# debugino.net
KiCad netlist of a schematic drawn in EAGLE
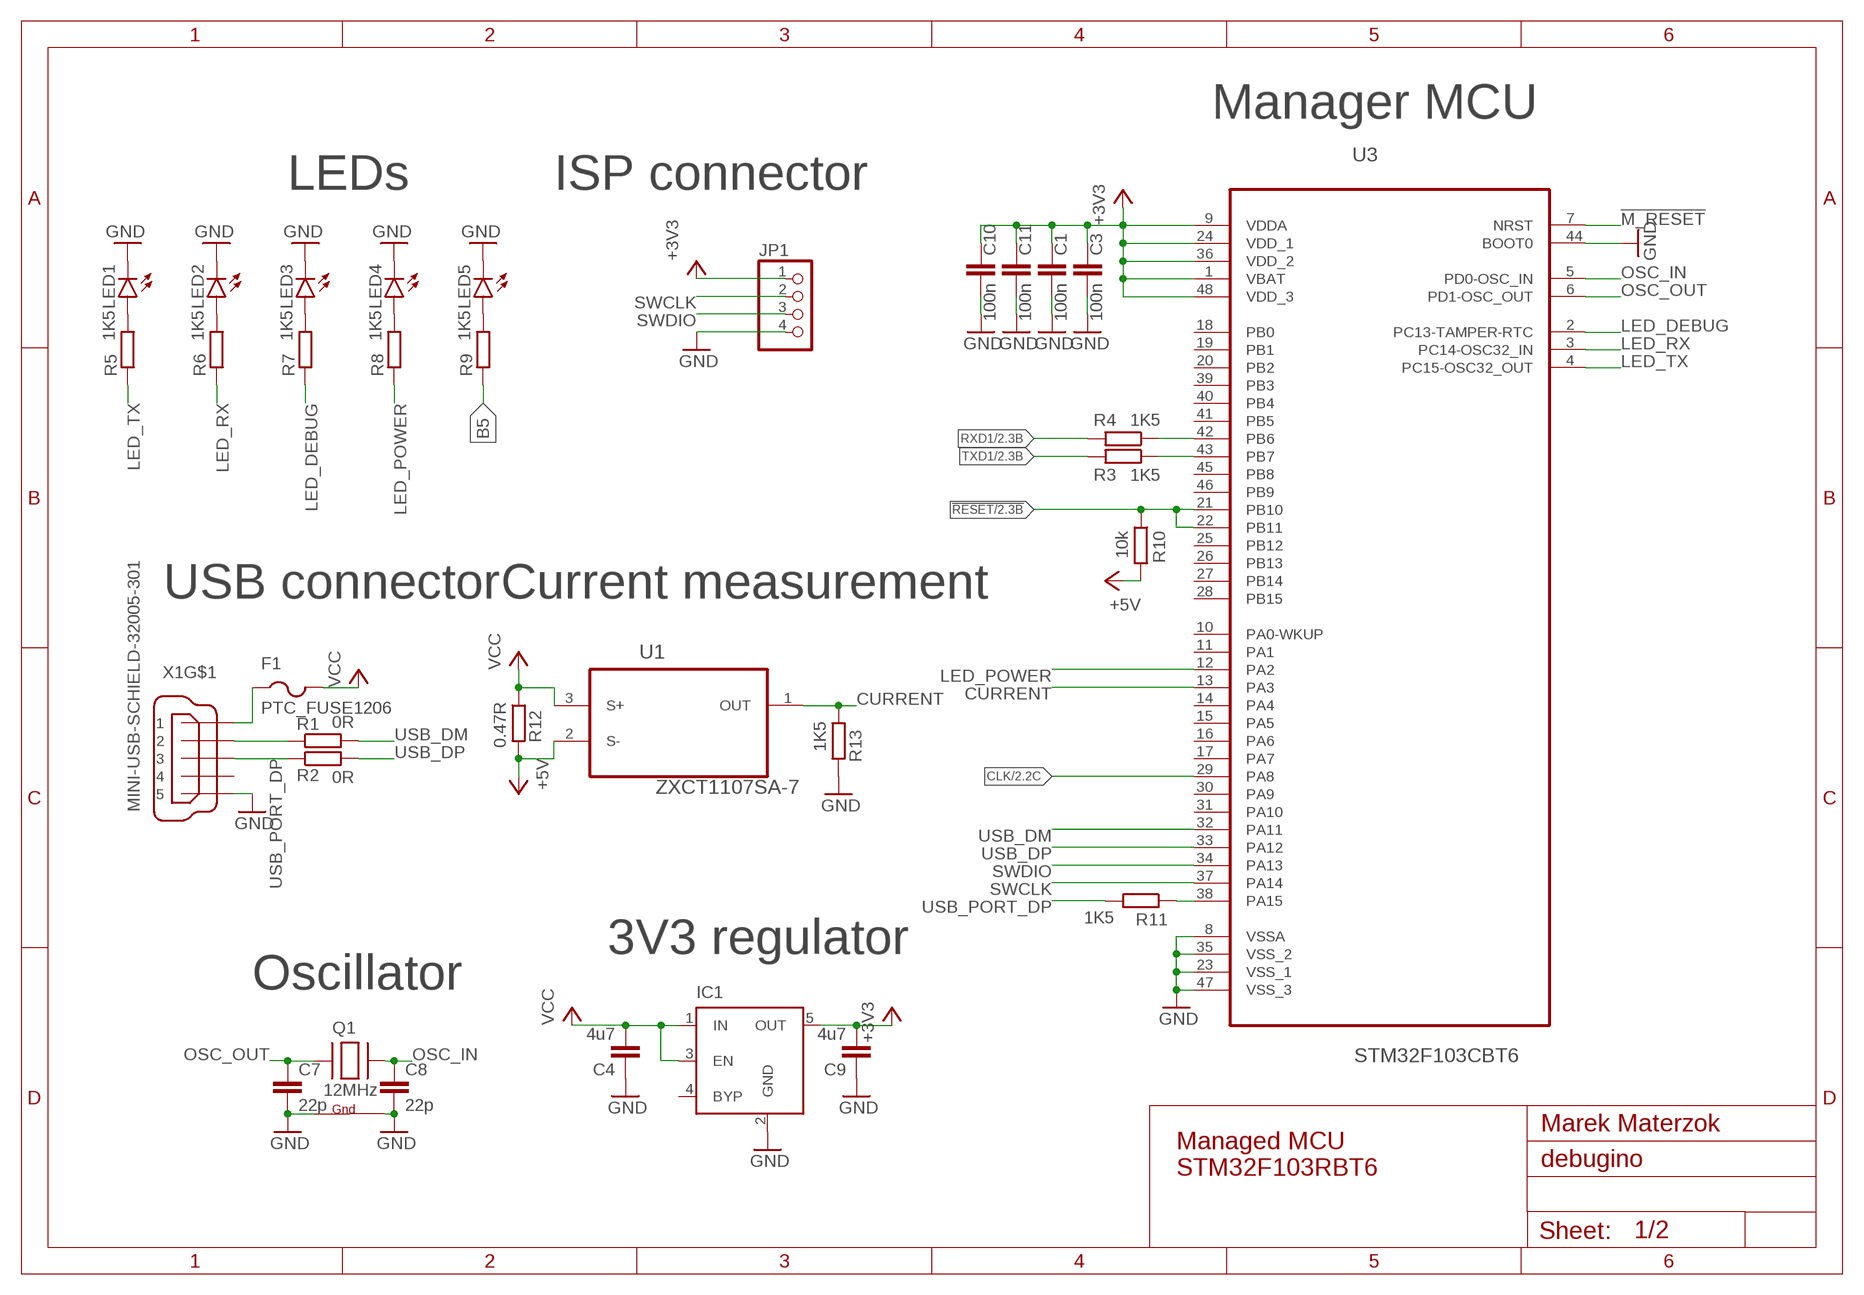
[diagram p0: schematic, sheet 1]
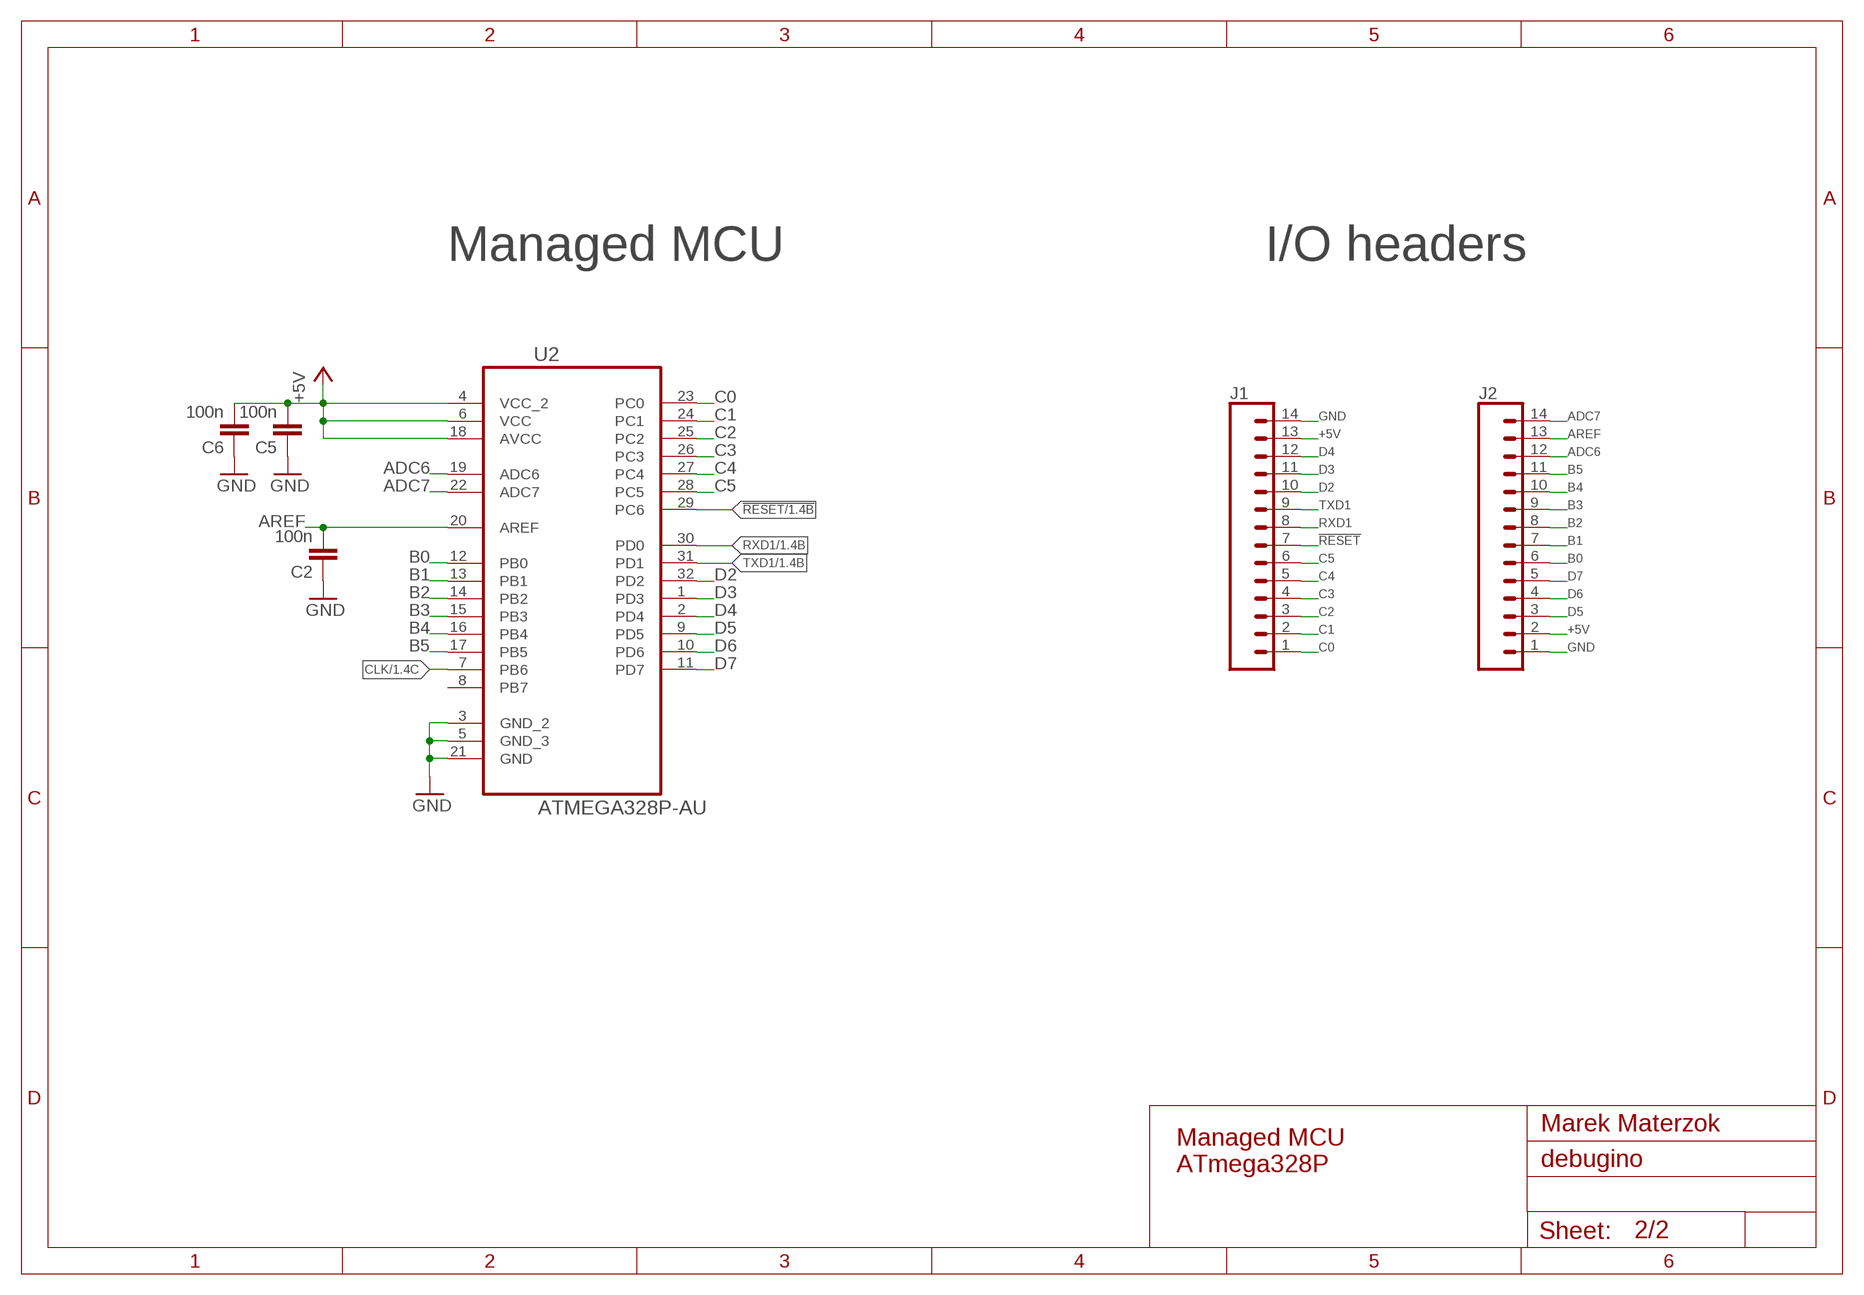
[diagram p1: schematic, sheet 2]

(export (version "E")
  (design (tool "Eeschema 10.0.6"))
  (components
    (comp (ref "C1")
      (value "100n")
      (footprint "eagle-import:CAPC1008X70M")
      (libsource (lib "eagle-import") (part "CAPACITOR0402"))
    )
    (comp (ref "C3")
      (value "100n")
      (footprint "eagle-import:CAPC1008X70M")
      (libsource (lib "eagle-import") (part "CAPACITOR0402"))
    )
    (comp (ref "C4")
      (value "4u7")
      (footprint "eagle-import:CAPC1608X100M")
      (libsource (lib "eagle-import") (part "CAPACITOR0603"))
    )
    (comp (ref "C7")
      (value "22p")
      (footprint "eagle-import:CAPC1008X70M")
      (libsource (lib "eagle-import") (part "CAPACITOR0402"))
    )
    (comp (ref "C8")
      (value "22p")
      (footprint "eagle-import:CAPC1008X70M")
      (libsource (lib "eagle-import") (part "CAPACITOR0402"))
    )
    (comp (ref "C9")
      (value "4u7")
      (footprint "eagle-import:CAPC1608X100M")
      (libsource (lib "eagle-import") (part "CAPACITOR0603"))
    )
    (comp (ref "C10")
      (value "100n")
      (footprint "eagle-import:CAPC1008X70M")
      (libsource (lib "eagle-import") (part "CAPACITOR0402"))
    )
    (comp (ref "C11")
      (value "100n")
      (footprint "eagle-import:CAPC1008X70M")
      (libsource (lib "eagle-import") (part "CAPACITOR0402"))
    )
    (comp (ref "F1")
      (value "PTC_FUSE1206")
      (footprint "eagle-import:FUSC3216X100M")
      (libsource (lib "eagle-import") (part "PTC_FUSE1206"))
    )
    (comp (ref "IC1")
      (value "MIC5219XX")
      (footprint "eagle-import:SOT23-5")
      (libsource (lib "eagle-import") (part "MIC5219XX"))
    )
    (comp (ref "JP1")
      (value "PINHD-1X4")
      (footprint "eagle-import:1X04")
      (libsource (lib "eagle-import") (part "PINHD-1X4"))
    )
    (comp (ref "LED1")
      (value "LEDCHIP-LED0603")
      (footprint "eagle-import:CHIP-LED0603")
      (libsource (lib "eagle-import") (part "LEDCHIP-LED0603"))
    )
    (comp (ref "LED2")
      (value "LEDCHIP-LED0603")
      (footprint "eagle-import:CHIP-LED0603")
      (libsource (lib "eagle-import") (part "LEDCHIP-LED0603"))
    )
    (comp (ref "LED3")
      (value "LEDCHIP-LED0603")
      (footprint "eagle-import:CHIP-LED0603")
      (libsource (lib "eagle-import") (part "LEDCHIP-LED0603"))
    )
    (comp (ref "LED4")
      (value "LEDCHIP-LED0603")
      (footprint "eagle-import:CHIP-LED0603")
      (libsource (lib "eagle-import") (part "LEDCHIP-LED0603"))
    )
    (comp (ref "LED5")
      (value "LEDCHIP-LED0603")
      (footprint "eagle-import:CHIP-LED0603")
      (libsource (lib "eagle-import") (part "LEDCHIP-LED0603"))
    )
    (comp (ref "Q1")
      (value "12MHz")
      (footprint "eagle-import:NX3225")
      (libsource (lib "eagle-import") (part "XTAL-4-3225"))
    )
    (comp (ref "R1")
      (value "0R")
      (footprint "eagle-import:RESC1608X55M")
      (libsource (lib "eagle-import") (part "RESISTOR0603"))
    )
    (comp (ref "R2")
      (value "0R")
      (footprint "eagle-import:RESC1608X55M")
      (libsource (lib "eagle-import") (part "RESISTOR0603"))
    )
    (comp (ref "R3")
      (value "1K5")
      (footprint "eagle-import:RESC1608X55M")
      (libsource (lib "eagle-import") (part "RESISTOR0603"))
    )
    (comp (ref "R4")
      (value "1K5")
      (footprint "eagle-import:RESC1608X55M")
      (libsource (lib "eagle-import") (part "RESISTOR0603"))
    )
    (comp (ref "R5")
      (value "1K5")
      (footprint "eagle-import:RESC1608X55M")
      (libsource (lib "eagle-import") (part "RESISTOR0603"))
    )
    (comp (ref "R6")
      (value "1K5")
      (footprint "eagle-import:RESC1608X55M")
      (libsource (lib "eagle-import") (part "RESISTOR0603"))
    )
    (comp (ref "R7")
      (value "1K5")
      (footprint "eagle-import:RESC1608X55M")
      (libsource (lib "eagle-import") (part "RESISTOR0603"))
    )
    (comp (ref "R8")
      (value "1K5")
      (footprint "eagle-import:RESC1608X55M")
      (libsource (lib "eagle-import") (part "RESISTOR0603"))
    )
    (comp (ref "R9")
      (value "1K5")
      (footprint "eagle-import:RESC1608X55M")
      (libsource (lib "eagle-import") (part "RESISTOR0603"))
    )
    (comp (ref "R10")
      (value "10k")
      (footprint "eagle-import:RESC1608X55M")
      (libsource (lib "eagle-import") (part "RESISTOR0603"))
    )
    (comp (ref "R11")
      (value "1K5")
      (footprint "eagle-import:RESC1608X55M")
      (libsource (lib "eagle-import") (part "RESISTOR0603"))
    )
    (comp (ref "R12")
      (value "0.47R")
      (footprint "eagle-import:RESC2012X65M")
      (libsource (lib "eagle-import") (part "RESISTOR0805"))
    )
    (comp (ref "R13")
      (value "1K5")
      (footprint "eagle-import:RESC1608X55M")
      (libsource (lib "eagle-import") (part "RESISTOR0603"))
    )
    (comp (ref "U1")
      (value "ZXCT1107SA-7")
      (footprint "eagle-import:SOT91P240X110-3N")
      (libsource (lib "eagle-import") (part "ZXCT1107SA-7"))
    )
    (comp (ref "U3")
      (value "STM32F103CBT6")
      (footprint "eagle-import:QFP50P900X900X160-48N")
      (libsource (lib "eagle-import") (part "STM32F103CBT6"))
    )
    (comp (ref "X1")
      (value "MINI-USB-SCHIELD-32005-301")
      (footprint "eagle-import:32005-301")
      (libsource (lib "eagle-import") (part "MINI-USB-SCHIELD-32005-301"))
    )
    (comp (ref "C2")
      (value "100n")
      (footprint "eagle-import:CAPC1008X70M")
      (libsource (lib "eagle-import") (part "CAPACITOR0402"))
    )
    (comp (ref "C5")
      (value "100n")
      (footprint "eagle-import:CAPC1008X70M")
      (libsource (lib "eagle-import") (part "CAPACITOR0402"))
    )
    (comp (ref "C6")
      (value "100n")
      (footprint "eagle-import:CAPC1008X70M")
      (libsource (lib "eagle-import") (part "CAPACITOR0402"))
    )
    (comp (ref "J1")
      (value "CONN_14")
      (footprint "eagle-import:1X14")
      (libsource (lib "eagle-import") (part "CONN_14"))
    )
    (comp (ref "J2")
      (value "CONN_14")
      (footprint "eagle-import:1X14")
      (libsource (lib "eagle-import") (part "CONN_14"))
    )
    (comp (ref "U2")
      (value "ATMEGA328P-AU")
      (footprint "eagle-import:QFP80P900X900X120-32N")
      (libsource (lib "eagle-import") (part "ATMEGA328P-AU"))
    )
  )
  (nets
    (net (code "1") (name "+3V3") (class "Default")
      (node (ref "C1") (pin "1") (pinfunction "1_1") (pintype "passive"))
      (node (ref "C10") (pin "1") (pinfunction "1_1") (pintype "passive"))
      (node (ref "C11") (pin "1") (pinfunction "1_1") (pintype "passive"))
      (node (ref "C3") (pin "1") (pinfunction "1_1") (pintype "passive"))
      (node (ref "C9") (pin "2") (pinfunction "2_2") (pintype "passive"))
      (node (ref "IC1") (pin "5") (pinfunction "OUT_5") (pintype "output"))
      (node (ref "JP1") (pin "1") (pinfunction "1_1") (pintype "passive"))
      (node (ref "U3") (pin "1") (pinfunction "VBAT_1") (pintype "input"))
      (node (ref "U3") (pin "24") (pinfunction "VDD_1_24") (pintype "bidirectional"))
      (node (ref "U3") (pin "36") (pinfunction "VDD_2_36") (pintype "power_in"))
      (node (ref "U3") (pin "48") (pinfunction "VDD_3_48") (pintype "power_in"))
      (node (ref "U3") (pin "9") (pinfunction "VDDA_9") (pintype "power_in"))
    )
    (net (code "2") (name "+5V") (class "Default")
      (node (ref "C5") (pin "2") (pinfunction "2_2") (pintype "passive"))
      (node (ref "C6") (pin "2") (pinfunction "2_2") (pintype "passive"))
      (node (ref "J1") (pin "13") (pinfunction "13_13") (pintype "passive"))
      (node (ref "J2") (pin "2") (pinfunction "2_2") (pintype "passive"))
      (node (ref "R10") (pin "2") (pinfunction "2_2") (pintype "passive"))
      (node (ref "R12") (pin "2") (pinfunction "2_2") (pintype "passive"))
      (node (ref "U1") (pin "2") (pinfunction "S-_2") (pintype "input"))
      (node (ref "U2") (pin "18") (pinfunction "AVCC_18") (pintype "power_in"))
      (node (ref "U2") (pin "4") (pinfunction "VCC_2_4") (pintype "power_in"))
      (node (ref "U2") (pin "6") (pinfunction "VCC_6") (pintype "power_in"))
    )
    (net (code "3") (name "ADC6") (class "Default")
      (node (ref "J2") (pin "12") (pinfunction "12_12") (pintype "passive"))
      (node (ref "U2") (pin "19") (pinfunction "ADC6_19") (pintype "input"))
    )
    (net (code "4") (name "ADC7") (class "Default")
      (node (ref "J2") (pin "14") (pinfunction "14_14") (pintype "passive"))
      (node (ref "U2") (pin "22") (pinfunction "ADC7_22") (pintype "input"))
    )
    (net (code "5") (name "AREF") (class "Default")
      (node (ref "C2") (pin "2") (pinfunction "2_2") (pintype "passive"))
      (node (ref "J2") (pin "13") (pinfunction "13_13") (pintype "passive"))
      (node (ref "U2") (pin "20") (pinfunction "AREF_20") (pintype "input"))
    )
    (net (code "6") (name "B0") (class "Default")
      (node (ref "J2") (pin "6") (pinfunction "6_6") (pintype "passive"))
      (node (ref "U2") (pin "12") (pinfunction "PB0_12") (pintype "bidirectional"))
    )
    (net (code "7") (name "B1") (class "Default")
      (node (ref "J2") (pin "7") (pinfunction "7_7") (pintype "passive"))
      (node (ref "U2") (pin "13") (pinfunction "PB1_13") (pintype "bidirectional"))
    )
    (net (code "8") (name "B2") (class "Default")
      (node (ref "J2") (pin "8") (pinfunction "8_8") (pintype "passive"))
      (node (ref "U2") (pin "14") (pinfunction "PB2_14") (pintype "bidirectional"))
    )
    (net (code "9") (name "B3") (class "Default")
      (node (ref "J2") (pin "9") (pinfunction "9_9") (pintype "passive"))
      (node (ref "U2") (pin "15") (pinfunction "PB3_15") (pintype "bidirectional"))
    )
    (net (code "10") (name "B4") (class "Default")
      (node (ref "J2") (pin "10") (pinfunction "10_10") (pintype "passive"))
      (node (ref "U2") (pin "16") (pinfunction "PB4_16") (pintype "bidirectional"))
    )
    (net (code "11") (name "B5") (class "Default")
      (node (ref "J2") (pin "11") (pinfunction "11_11") (pintype "passive"))
      (node (ref "R9") (pin "1") (pinfunction "1_1") (pintype "passive"))
      (node (ref "U2") (pin "17") (pinfunction "PB5_17") (pintype "bidirectional"))
    )
    (net (code "12") (name "C0") (class "Default")
      (node (ref "J1") (pin "1") (pinfunction "1_1") (pintype "passive"))
      (node (ref "U2") (pin "23") (pinfunction "PC0_23") (pintype "bidirectional"))
    )
    (net (code "13") (name "C1") (class "Default")
      (node (ref "J1") (pin "2") (pinfunction "2_2") (pintype "passive"))
      (node (ref "U2") (pin "24") (pinfunction "PC1_24") (pintype "bidirectional"))
    )
    (net (code "14") (name "C2") (class "Default")
      (node (ref "J1") (pin "3") (pinfunction "3_3") (pintype "passive"))
      (node (ref "U2") (pin "25") (pinfunction "PC2_25") (pintype "bidirectional"))
    )
    (net (code "15") (name "C3") (class "Default")
      (node (ref "J1") (pin "4") (pinfunction "4_4") (pintype "passive"))
      (node (ref "U2") (pin "26") (pinfunction "PC3_26") (pintype "bidirectional"))
    )
    (net (code "16") (name "C4") (class "Default")
      (node (ref "J1") (pin "5") (pinfunction "5_5") (pintype "passive"))
      (node (ref "U2") (pin "27") (pinfunction "PC4_27") (pintype "bidirectional"))
    )
    (net (code "17") (name "C5") (class "Default")
      (node (ref "J1") (pin "6") (pinfunction "6_6") (pintype "passive"))
      (node (ref "U2") (pin "28") (pinfunction "PC5_28") (pintype "bidirectional"))
    )
    (net (code "18") (name "CLK") (class "Default")
      (node (ref "U2") (pin "7") (pinfunction "PB6_7") (pintype "bidirectional"))
      (node (ref "U3") (pin "29") (pinfunction "PA8_29") (pintype "bidirectional"))
    )
    (net (code "19") (name "CURRENT") (class "Default")
      (node (ref "R13") (pin "1") (pinfunction "1_1") (pintype "passive"))
      (node (ref "U1") (pin "1") (pinfunction "OUT_1") (pintype "output"))
      (node (ref "U3") (pin "13") (pinfunction "PA3_13") (pintype "bidirectional"))
    )
    (net (code "20") (name "D2") (class "Default")
      (node (ref "J1") (pin "10") (pinfunction "10_10") (pintype "passive"))
      (node (ref "U2") (pin "32") (pinfunction "PD2_32") (pintype "bidirectional"))
    )
    (net (code "21") (name "D3") (class "Default")
      (node (ref "J1") (pin "11") (pinfunction "11_11") (pintype "passive"))
      (node (ref "U2") (pin "1") (pinfunction "PD3_1") (pintype "bidirectional"))
    )
    (net (code "22") (name "D4") (class "Default")
      (node (ref "J1") (pin "12") (pinfunction "12_12") (pintype "passive"))
      (node (ref "U2") (pin "2") (pinfunction "PD4_2") (pintype "bidirectional"))
    )
    (net (code "23") (name "D5") (class "Default")
      (node (ref "J2") (pin "3") (pinfunction "3_3") (pintype "passive"))
      (node (ref "U2") (pin "9") (pinfunction "PD5_9") (pintype "bidirectional"))
    )
    (net (code "24") (name "D6") (class "Default")
      (node (ref "J2") (pin "4") (pinfunction "4_4") (pintype "passive"))
      (node (ref "U2") (pin "10") (pinfunction "PD6_10") (pintype "bidirectional"))
    )
    (net (code "25") (name "D7") (class "Default")
      (node (ref "J2") (pin "5") (pinfunction "5_5") (pintype "passive"))
      (node (ref "U2") (pin "11") (pinfunction "PD7_11") (pintype "bidirectional"))
    )
    (net (code "26") (name "GND") (class "Default")
      (node (ref "C1") (pin "2") (pinfunction "2_2") (pintype "passive"))
      (node (ref "C10") (pin "2") (pinfunction "2_2") (pintype "passive"))
      (node (ref "C11") (pin "2") (pinfunction "2_2") (pintype "passive"))
      (node (ref "C2") (pin "1") (pinfunction "1_1") (pintype "passive"))
      (node (ref "C3") (pin "2") (pinfunction "2_2") (pintype "passive"))
      (node (ref "C4") (pin "1") (pinfunction "1_1") (pintype "passive"))
      (node (ref "C5") (pin "1") (pinfunction "1_1") (pintype "passive"))
      (node (ref "C6") (pin "1") (pinfunction "1_1") (pintype "passive"))
      (node (ref "C7") (pin "2") (pinfunction "2_2") (pintype "passive"))
      (node (ref "C8") (pin "2") (pinfunction "2_2") (pintype "passive"))
      (node (ref "C9") (pin "1") (pinfunction "1_1") (pintype "passive"))
      (node (ref "IC1") (pin "2") (pinfunction "GND_2") (pintype "power_in"))
      (node (ref "J1") (pin "14") (pinfunction "14_14") (pintype "passive"))
      (node (ref "J2") (pin "1") (pinfunction "1_1") (pintype "passive"))
      (node (ref "JP1") (pin "4") (pinfunction "4_4") (pintype "passive"))
      (node (ref "LED1") (pin "C") (pinfunction "C_C") (pintype "passive"))
      (node (ref "LED2") (pin "C") (pinfunction "C_C") (pintype "passive"))
      (node (ref "LED3") (pin "C") (pinfunction "C_C") (pintype "passive"))
      (node (ref "LED4") (pin "C") (pinfunction "C_C") (pintype "passive"))
      (node (ref "LED5") (pin "C") (pinfunction "C_C") (pintype "passive"))
      (node (ref "Q1") (pin "2") (pinfunction "G2_2") (pintype "power_in"))
      (node (ref "Q1") (pin "4") (pinfunction "G1_4") (pintype "power_in"))
      (node (ref "R13") (pin "2") (pinfunction "2_2") (pintype "passive"))
      (node (ref "U2") (pin "21") (pinfunction "GND_21") (pintype "passive"))
      (node (ref "U2") (pin "3") (pinfunction "GND_2_3") (pintype "passive"))
      (node (ref "U2") (pin "5") (pinfunction "GND_3_5") (pintype "passive"))
      (node (ref "U3") (pin "23") (pinfunction "VSS_1_23") (pintype "bidirectional"))
      (node (ref "U3") (pin "35") (pinfunction "VSS_2_35") (pintype "passive"))
      (node (ref "U3") (pin "44") (pinfunction "BOOT0_44") (pintype "bidirectional"))
      (node (ref "U3") (pin "47") (pinfunction "VSS_3_47") (pintype "passive"))
      (node (ref "U3") (pin "8") (pinfunction "VSSA_8") (pintype "passive"))
      (node (ref "X1") (pin "5") (pinfunction "5_5") (pintype "passive"))
    )
    (net (code "27") (name "LED_DEBUG") (class "Default")
      (node (ref "R7") (pin "1") (pinfunction "1_1") (pintype "passive"))
      (node (ref "U3") (pin "2") (pinfunction "PC13-TAMPER-RTC_2") (pintype "bidirectional"))
    )
    (net (code "28") (name "LED_POWER") (class "Default")
      (node (ref "R8") (pin "1") (pinfunction "1_1") (pintype "passive"))
      (node (ref "U3") (pin "12") (pinfunction "PA2_12") (pintype "bidirectional"))
    )
    (net (code "29") (name "LED_RX") (class "Default")
      (node (ref "R6") (pin "1") (pinfunction "1_1") (pintype "passive"))
      (node (ref "U3") (pin "3") (pinfunction "PC14-OSC32_IN_3") (pintype "bidirectional"))
    )
    (net (code "30") (name "LED_TX") (class "Default")
      (node (ref "R5") (pin "1") (pinfunction "1_1") (pintype "passive"))
      (node (ref "U3") (pin "4") (pinfunction "PC15-OSC32_OUT_4") (pintype "bidirectional"))
    )
    (net (code "31") (name "Net-(F1-Pad1)") (class "Default")
      (node (ref "F1") (pin "1") (pinfunction "1_1") (pintype "passive"))
      (node (ref "X1") (pin "1") (pinfunction "1_1") (pintype "passive"))
    )
    (net (code "32") (name "Net-(LED1-PadA)") (class "Default")
      (node (ref "LED1") (pin "A") (pinfunction "A_A") (pintype "passive"))
      (node (ref "R5") (pin "2") (pinfunction "2_2") (pintype "passive"))
    )
    (net (code "33") (name "Net-(LED2-PadA)") (class "Default")
      (node (ref "LED2") (pin "A") (pinfunction "A_A") (pintype "passive"))
      (node (ref "R6") (pin "2") (pinfunction "2_2") (pintype "passive"))
    )
    (net (code "34") (name "Net-(LED3-PadA)") (class "Default")
      (node (ref "LED3") (pin "A") (pinfunction "A_A") (pintype "passive"))
      (node (ref "R7") (pin "2") (pinfunction "2_2") (pintype "passive"))
    )
    (net (code "35") (name "Net-(LED4-PadA)") (class "Default")
      (node (ref "LED4") (pin "A") (pinfunction "A_A") (pintype "passive"))
      (node (ref "R8") (pin "2") (pinfunction "2_2") (pintype "passive"))
    )
    (net (code "36") (name "Net-(LED5-PadA)") (class "Default")
      (node (ref "LED5") (pin "A") (pinfunction "A_A") (pintype "passive"))
      (node (ref "R9") (pin "2") (pinfunction "2_2") (pintype "passive"))
    )
    (net (code "37") (name "Net-(R1-Pad1)") (class "Default")
      (node (ref "R1") (pin "1") (pinfunction "1_1") (pintype "passive"))
      (node (ref "X1") (pin "2") (pinfunction "2_2") (pintype "passive"))
    )
    (net (code "38") (name "Net-(U3-PA15)") (class "Default")
      (node (ref "R11") (pin "1") (pinfunction "1_1") (pintype "passive"))
      (node (ref "U3") (pin "38") (pinfunction "PA15_38") (pintype "bidirectional"))
    )
    (net (code "39") (name "Net-(U3-PB6)") (class "Default")
      (node (ref "R4") (pin "1") (pinfunction "1_1") (pintype "passive"))
      (node (ref "U3") (pin "42") (pinfunction "PB6_42") (pintype "bidirectional"))
    )
    (net (code "40") (name "Net-(U3-PB7)") (class "Default")
      (node (ref "R3") (pin "1") (pinfunction "1_1") (pintype "passive"))
      (node (ref "U3") (pin "43") (pinfunction "PB7_43") (pintype "bidirectional"))
    )
    (net (code "41") (name "OSC_IN") (class "Default")
      (node (ref "C8") (pin "1") (pinfunction "1_1") (pintype "passive"))
      (node (ref "Q1") (pin "3") (pinfunction "X2_3") (pintype "bidirectional"))
      (node (ref "U3") (pin "5") (pinfunction "PD0-OSC_IN_5") (pintype "bidirectional"))
    )
    (net (code "42") (name "OSC_OUT") (class "Default")
      (node (ref "C7") (pin "1") (pinfunction "1_1") (pintype "passive"))
      (node (ref "Q1") (pin "1") (pinfunction "X1_1") (pintype "bidirectional"))
      (node (ref "U3") (pin "6") (pinfunction "PD1-OSC_OUT_6") (pintype "bidirectional"))
    )
    (net (code "43") (name "RXD1") (class "Default")
      (node (ref "J1") (pin "8") (pinfunction "8_8") (pintype "passive"))
      (node (ref "R4") (pin "2") (pinfunction "2_2") (pintype "passive"))
      (node (ref "U2") (pin "30") (pinfunction "PD0_30") (pintype "bidirectional"))
    )
    (net (code "44") (name "SWCLK") (class "Default")
      (node (ref "JP1") (pin "2") (pinfunction "2_2") (pintype "passive"))
      (node (ref "U3") (pin "37") (pinfunction "PA14_37") (pintype "bidirectional"))
    )
    (net (code "45") (name "SWDIO") (class "Default")
      (node (ref "JP1") (pin "3") (pinfunction "3_3") (pintype "passive"))
      (node (ref "U3") (pin "34") (pinfunction "PA13_34") (pintype "bidirectional"))
    )
    (net (code "46") (name "TXD1") (class "Default")
      (node (ref "J1") (pin "9") (pinfunction "9_9") (pintype "passive"))
      (node (ref "R3") (pin "2") (pinfunction "2_2") (pintype "passive"))
      (node (ref "U2") (pin "31") (pinfunction "PD1_31") (pintype "bidirectional"))
    )
    (net (code "47") (name "USB_DM") (class "Default")
      (node (ref "R1") (pin "2") (pinfunction "2_2") (pintype "passive"))
      (node (ref "U3") (pin "32") (pinfunction "PA11_32") (pintype "power_in"))
    )
    (net (code "48") (name "USB_DP") (class "Default")
      (node (ref "R2") (pin "2") (pinfunction "2_2") (pintype "passive"))
      (node (ref "U3") (pin "33") (pinfunction "PA12_33") (pintype "bidirectional"))
    )
    (net (code "49") (name "USB_PORT_DP") (class "Default")
      (node (ref "R11") (pin "2") (pinfunction "2_2") (pintype "passive"))
      (node (ref "R2") (pin "1") (pinfunction "1_1") (pintype "passive"))
      (node (ref "X1") (pin "3") (pinfunction "3_3") (pintype "passive"))
    )
    (net (code "50") (name "VCC") (class "Default")
      (node (ref "C4") (pin "2") (pinfunction "2_2") (pintype "passive"))
      (node (ref "F1") (pin "2") (pinfunction "2_2") (pintype "passive"))
      (node (ref "IC1") (pin "1") (pinfunction "IN_1") (pintype "input"))
      (node (ref "IC1") (pin "3") (pinfunction "EN_3") (pintype "input"))
      (node (ref "R12") (pin "1") (pinfunction "1_1") (pintype "passive"))
      (node (ref "U1") (pin "3") (pinfunction "S+_3") (pintype "input"))
    )
    (net (code "51") (name "unconnected-(IC1-BYP-Pad4)") (class "Default")
      (node (ref "IC1") (pin "4") (pinfunction "BYP_4") (pintype "passive"))
    )
    (net (code "52") (name "unconnected-(U2-PB7-Pad8)") (class "Default")
      (node (ref "U2") (pin "8") (pinfunction "PB7_8") (pintype "bidirectional"))
    )
    (net (code "53") (name "unconnected-(U3-PA0-WKUP-Pad10)") (class "Default")
      (node (ref "U3") (pin "10") (pinfunction "PA0-WKUP_10") (pintype "bidirectional"))
    )
    (net (code "54") (name "unconnected-(U3-PA1-Pad11)") (class "Default")
      (node (ref "U3") (pin "11") (pinfunction "PA1_11") (pintype "bidirectional"))
    )
    (net (code "55") (name "unconnected-(U3-PA4-Pad14)") (class "Default")
      (node (ref "U3") (pin "14") (pinfunction "PA4_14") (pintype "bidirectional"))
    )
    (net (code "56") (name "unconnected-(U3-PA5-Pad15)") (class "Default")
      (node (ref "U3") (pin "15") (pinfunction "PA5_15") (pintype "bidirectional"))
    )
    (net (code "57") (name "unconnected-(U3-PA6-Pad16)") (class "Default")
      (node (ref "U3") (pin "16") (pinfunction "PA6_16") (pintype "bidirectional"))
    )
    (net (code "58") (name "unconnected-(U3-PA7-Pad17)") (class "Default")
      (node (ref "U3") (pin "17") (pinfunction "PA7_17") (pintype "bidirectional"))
    )
    (net (code "59") (name "unconnected-(U3-PA9-Pad30)") (class "Default")
      (node (ref "U3") (pin "30") (pinfunction "PA9_30") (pintype "bidirectional"))
    )
    (net (code "60") (name "unconnected-(U3-PA10-Pad31)") (class "Default")
      (node (ref "U3") (pin "31") (pinfunction "PA10_31") (pintype "bidirectional"))
    )
    (net (code "61") (name "unconnected-(U3-PB0-Pad18)") (class "Default")
      (node (ref "U3") (pin "18") (pinfunction "PB0_18") (pintype "bidirectional"))
    )
    (net (code "62") (name "unconnected-(U3-PB1-Pad19)") (class "Default")
      (node (ref "U3") (pin "19") (pinfunction "PB1_19") (pintype "bidirectional"))
    )
    (net (code "63") (name "unconnected-(U3-PB2-Pad20)") (class "Default")
      (node (ref "U3") (pin "20") (pinfunction "PB2_20") (pintype "bidirectional"))
    )
    (net (code "64") (name "unconnected-(U3-PB3-Pad39)") (class "Default")
      (node (ref "U3") (pin "39") (pinfunction "PB3_39") (pintype "bidirectional"))
    )
    (net (code "65") (name "unconnected-(U3-PB4-Pad40)") (class "Default")
      (node (ref "U3") (pin "40") (pinfunction "PB4_40") (pintype "bidirectional"))
    )
    (net (code "66") (name "unconnected-(U3-PB5-Pad41)") (class "Default")
      (node (ref "U3") (pin "41") (pinfunction "PB5_41") (pintype "bidirectional"))
    )
    (net (code "67") (name "unconnected-(U3-PB8-Pad45)") (class "Default")
      (node (ref "U3") (pin "45") (pinfunction "PB8_45") (pintype "bidirectional"))
    )
    (net (code "68") (name "unconnected-(U3-PB9-Pad46)") (class "Default")
      (node (ref "U3") (pin "46") (pinfunction "PB9_46") (pintype "bidirectional"))
    )
    (net (code "69") (name "unconnected-(U3-PB12-Pad25)") (class "Default")
      (node (ref "U3") (pin "25") (pinfunction "PB12_25") (pintype "bidirectional"))
    )
    (net (code "70") (name "unconnected-(U3-PB13-Pad26)") (class "Default")
      (node (ref "U3") (pin "26") (pinfunction "PB13_26") (pintype "bidirectional"))
    )
    (net (code "71") (name "unconnected-(U3-PB14-Pad27)") (class "Default")
      (node (ref "U3") (pin "27") (pinfunction "PB14_27") (pintype "bidirectional"))
    )
    (net (code "72") (name "unconnected-(U3-PB15-Pad28)") (class "Default")
      (node (ref "U3") (pin "28") (pinfunction "PB15_28") (pintype "bidirectional"))
    )
    (net (code "73") (name "unconnected-(X1-Pad4)") (class "Default")
      (node (ref "X1") (pin "4") (pinfunction "4_4") (pintype "passive"))
    )
    (net (code "74") (name "~{M_RESET}") (class "Default")
      (node (ref "U3") (pin "7") (pinfunction "NRST_7") (pintype "bidirectional"))
    )
    (net (code "75") (name "~{RESET}") (class "Default")
      (node (ref "J1") (pin "7") (pinfunction "7_7") (pintype "passive"))
      (node (ref "R10") (pin "1") (pinfunction "1_1") (pintype "passive"))
      (node (ref "U2") (pin "29") (pinfunction "PC6_29") (pintype "bidirectional"))
      (node (ref "U3") (pin "21") (pinfunction "PB10_21") (pintype "bidirectional"))
      (node (ref "U3") (pin "22") (pinfunction "PB11_22") (pintype "bidirectional"))
    )
  )
)
